# frets-main-board.net
KiCad netlist of a schematic drawn in EAGLE
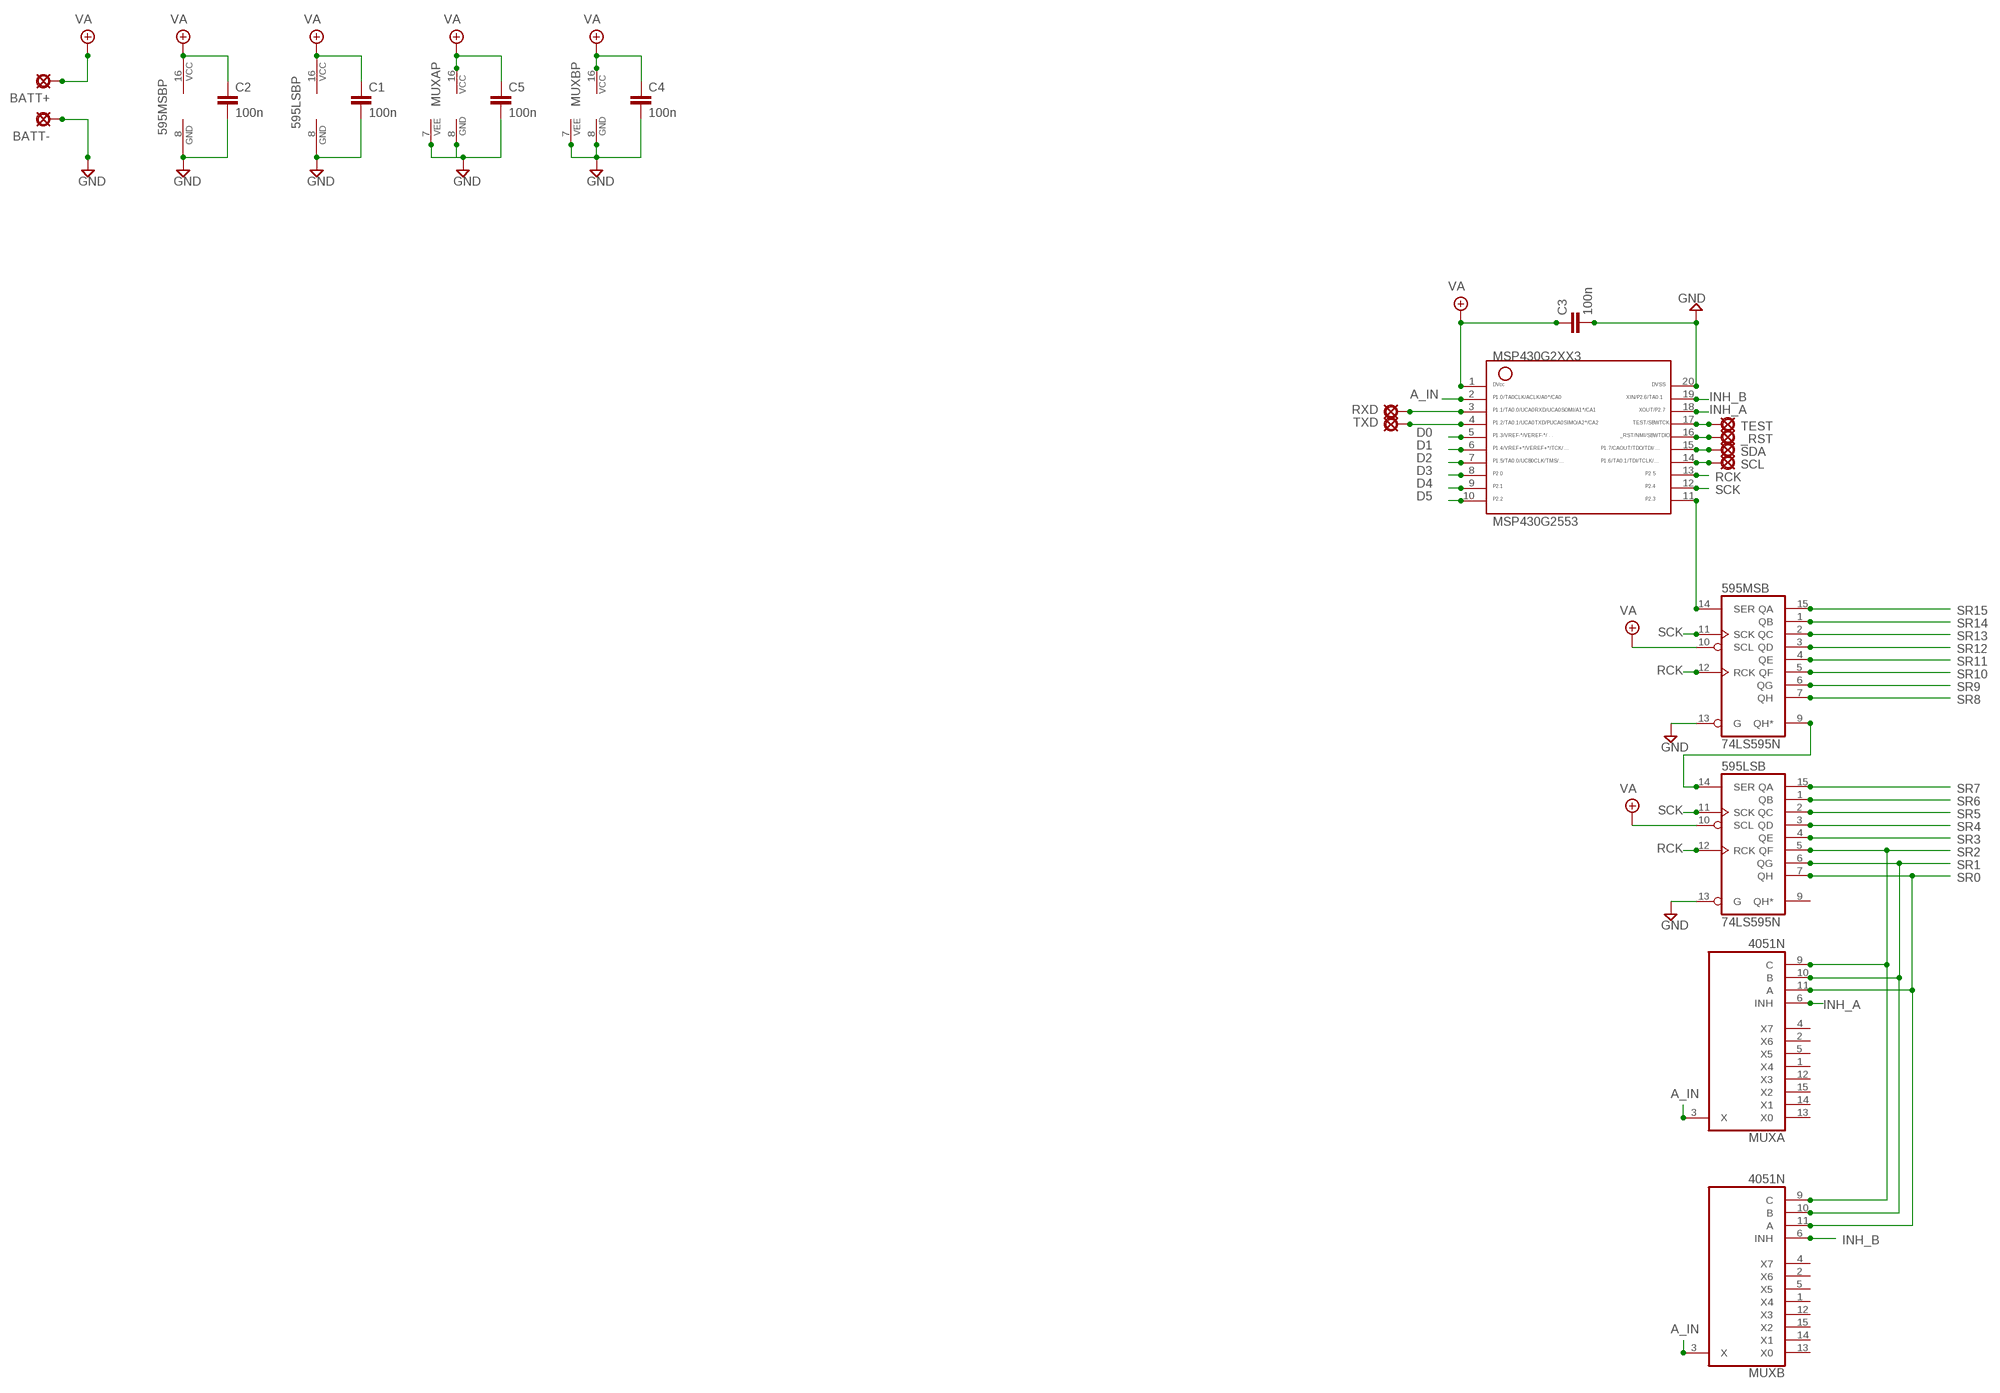
[diagram p0: schematic, sheet 1]

(export (version "E")
  (design (tool "Eeschema 10.0.6"))
  (components
    (comp (ref "595LSB")
      (value "74LS595N")
      (footprint "eagle-import:DIL16")
      (libsource (lib "eagle-import") (part "74595NLS"))
    )
    (comp (ref "595MSB")
      (value "74LS595N")
      (footprint "eagle-import:DIL16")
      (libsource (lib "eagle-import") (part "74595NLS"))
    )
    (comp (ref "BATT+")
      (value "PADL")
      (footprint "eagle-import:LONG")
      (libsource (lib "eagle-import") (part "PADL"))
    )
    (comp (ref "BATT-")
      (value "PADL")
      (footprint "eagle-import:LONG")
      (libsource (lib "eagle-import") (part "PADL"))
    )
    (comp (ref "C1")
      (value "100n")
      (footprint "eagle-import:050X030_050_3")
      (libsource (lib "eagle-import") (part "050X030_050"))
    )
    (comp (ref "C2")
      (value "100n")
      (footprint "eagle-import:050X030_050_3")
      (libsource (lib "eagle-import") (part "050X030_050"))
    )
    (comp (ref "C3")
      (value "100n")
      (footprint "eagle-import:050X030_050_3")
      (libsource (lib "eagle-import") (part "050X030_050"))
    )
    (comp (ref "C4")
      (value "100n")
      (footprint "eagle-import:050X030_050_3")
      (libsource (lib "eagle-import") (part "050X030_050"))
    )
    (comp (ref "C5")
      (value "100n")
      (footprint "eagle-import:050X030_050_3")
      (libsource (lib "eagle-import") (part "050X030_050"))
    )
    (comp (ref "MSP430G2553")
      (value "G2XX3---N20")
      (footprint "eagle-import:N20")
      (libsource (lib "eagle-import") (part "G2XX3---N20"))
    )
    (comp (ref "MUXA")
      (value "4051N")
      (footprint "eagle-import:DIL16")
      (libsource (lib "eagle-import") (part "4051N"))
    )
    (comp (ref "MUXB")
      (value "4051N")
      (footprint "eagle-import:DIL16")
      (libsource (lib "eagle-import") (part "4051N"))
    )
    (comp (ref "RXD")
      (value "PAD")
      (footprint "eagle-import:SQUARE")
      (libsource (lib "eagle-import") (part "PAD"))
    )
    (comp (ref "SCL")
      (value "PAD")
      (footprint "eagle-import:SQUARE")
      (libsource (lib "eagle-import") (part "PAD"))
    )
    (comp (ref "SDA")
      (value "PAD8")
      (footprint "eagle-import:OCTOGON")
      (libsource (lib "eagle-import") (part "PAD8"))
    )
    (comp (ref "TEST")
      (value "PAD8")
      (footprint "eagle-import:OCTOGON")
      (libsource (lib "eagle-import") (part "PAD8"))
    )
    (comp (ref "TXD")
      (value "PAD8")
      (footprint "eagle-import:OCTOGON")
      (libsource (lib "eagle-import") (part "PAD8"))
    )
    (comp (ref "_RST")
      (value "PAD")
      (footprint "eagle-import:SQUARE")
      (libsource (lib "eagle-import") (part "PAD"))
    )
  )
  (nets
    (net (code "1") (name "/A_IN") (class "Default")
      (node (ref "MSP430G2553") (pin "2") (pinfunction "2_2") (pintype "bidirectional"))
      (node (ref "MUXA") (pin "3") (pinfunction "X_3") (pintype "bidirectional"))
      (node (ref "MUXB") (pin "3") (pinfunction "X_3") (pintype "bidirectional"))
    )
    (net (code "2") (name "/D0") (class "Default")
      (node (ref "MSP430G2553") (pin "5") (pinfunction "5_5") (pintype "bidirectional"))
    )
    (net (code "3") (name "/D1") (class "Default")
      (node (ref "MSP430G2553") (pin "6") (pinfunction "6_6") (pintype "bidirectional"))
    )
    (net (code "4") (name "/D2") (class "Default")
      (node (ref "MSP430G2553") (pin "7") (pinfunction "7_7") (pintype "bidirectional"))
    )
    (net (code "5") (name "/D3") (class "Default")
      (node (ref "MSP430G2553") (pin "8") (pinfunction "8_8") (pintype "bidirectional"))
    )
    (net (code "6") (name "/D4") (class "Default")
      (node (ref "MSP430G2553") (pin "9") (pinfunction "9_9") (pintype "bidirectional"))
    )
    (net (code "7") (name "/D5") (class "Default")
      (node (ref "MSP430G2553") (pin "10") (pinfunction "10_10") (pintype "bidirectional"))
    )
    (net (code "8") (name "/INH_A") (class "Default")
      (node (ref "MSP430G2553") (pin "18") (pinfunction "18_18") (pintype "bidirectional"))
      (node (ref "MUXA") (pin "6") (pinfunction "INH_6") (pintype "input"))
    )
    (net (code "9") (name "/INH_B") (class "Default")
      (node (ref "MSP430G2553") (pin "19") (pinfunction "19_19") (pintype "bidirectional"))
      (node (ref "MUXB") (pin "6") (pinfunction "INH_6") (pintype "input"))
    )
    (net (code "10") (name "/RCK") (class "Default")
      (node (ref "595LSB") (pin "12") (pinfunction "RCK_12") (pintype "input"))
      (node (ref "595MSB") (pin "12") (pinfunction "RCK_12") (pintype "input"))
      (node (ref "MSP430G2553") (pin "13") (pinfunction "13_13") (pintype "bidirectional"))
    )
    (net (code "11") (name "/SCK") (class "Default")
      (node (ref "595LSB") (pin "11") (pinfunction "SCK_11") (pintype "input"))
      (node (ref "595MSB") (pin "11") (pinfunction "SCK_11") (pintype "input"))
      (node (ref "MSP430G2553") (pin "12") (pinfunction "12_12") (pintype "bidirectional"))
    )
    (net (code "12") (name "/SR0") (class "Default")
      (node (ref "595LSB") (pin "7") (pinfunction "QH_7") (pintype "tri_state"))
      (node (ref "MUXA") (pin "11") (pinfunction "A_11") (pintype "input"))
      (node (ref "MUXB") (pin "11") (pinfunction "A_11") (pintype "input"))
    )
    (net (code "13") (name "/SR1") (class "Default")
      (node (ref "595LSB") (pin "6") (pinfunction "QG_6") (pintype "tri_state"))
      (node (ref "MUXA") (pin "10") (pinfunction "B_10") (pintype "input"))
      (node (ref "MUXB") (pin "10") (pinfunction "B_10") (pintype "input"))
    )
    (net (code "14") (name "/SR2") (class "Default")
      (node (ref "595LSB") (pin "5") (pinfunction "QF_5") (pintype "tri_state"))
      (node (ref "MUXA") (pin "9") (pinfunction "C_9") (pintype "input"))
      (node (ref "MUXB") (pin "9") (pinfunction "C_9") (pintype "input"))
    )
    (net (code "15") (name "/SR3") (class "Default")
      (node (ref "595LSB") (pin "4") (pinfunction "QE_4") (pintype "tri_state"))
    )
    (net (code "16") (name "/SR4") (class "Default")
      (node (ref "595LSB") (pin "3") (pinfunction "QD_3") (pintype "tri_state"))
    )
    (net (code "17") (name "/SR5") (class "Default")
      (node (ref "595LSB") (pin "2") (pinfunction "QC_2") (pintype "tri_state"))
    )
    (net (code "18") (name "/SR6") (class "Default")
      (node (ref "595LSB") (pin "1") (pinfunction "QB_1") (pintype "tri_state"))
    )
    (net (code "19") (name "/SR7") (class "Default")
      (node (ref "595LSB") (pin "15") (pinfunction "QA_15") (pintype "tri_state"))
    )
    (net (code "20") (name "/SR8") (class "Default")
      (node (ref "595MSB") (pin "7") (pinfunction "QH_7") (pintype "tri_state"))
    )
    (net (code "21") (name "/SR9") (class "Default")
      (node (ref "595MSB") (pin "6") (pinfunction "QG_6") (pintype "tri_state"))
    )
    (net (code "22") (name "/SR10") (class "Default")
      (node (ref "595MSB") (pin "5") (pinfunction "QF_5") (pintype "tri_state"))
    )
    (net (code "23") (name "/SR11") (class "Default")
      (node (ref "595MSB") (pin "4") (pinfunction "QE_4") (pintype "tri_state"))
    )
    (net (code "24") (name "/SR12") (class "Default")
      (node (ref "595MSB") (pin "3") (pinfunction "QD_3") (pintype "tri_state"))
    )
    (net (code "25") (name "/SR13") (class "Default")
      (node (ref "595MSB") (pin "2") (pinfunction "QC_2") (pintype "tri_state"))
    )
    (net (code "26") (name "/SR14") (class "Default")
      (node (ref "595MSB") (pin "1") (pinfunction "QB_1") (pintype "tri_state"))
    )
    (net (code "27") (name "/SR15") (class "Default")
      (node (ref "595MSB") (pin "15") (pinfunction "QA_15") (pintype "tri_state"))
    )
    (net (code "28") (name "GND") (class "Default")
      (node (ref "595LSB") (pin "13") (pinfunction "G_13") (pintype "input"))
      (node (ref "595LSB") (pin "8") (pinfunction "GND_8") (pintype "power_in"))
      (node (ref "595MSB") (pin "13") (pinfunction "G_13") (pintype "input"))
      (node (ref "595MSB") (pin "8") (pinfunction "GND_8") (pintype "power_in"))
      (node (ref "BATT-") (pin "1") (pinfunction "PAD_1") (pintype "passive"))
      (node (ref "C1") (pin "2") (pinfunction "2_2") (pintype "passive"))
      (node (ref "C2") (pin "2") (pinfunction "2_2") (pintype "passive"))
      (node (ref "C3") (pin "2") (pinfunction "2_2") (pintype "passive"))
      (node (ref "C4") (pin "2") (pinfunction "2_2") (pintype "passive"))
      (node (ref "C5") (pin "2") (pinfunction "2_2") (pintype "passive"))
      (node (ref "MSP430G2553") (pin "20") (pinfunction "20_20") (pintype "bidirectional"))
      (node (ref "MUXA") (pin "7") (pinfunction "VEE_7") (pintype "power_in"))
      (node (ref "MUXA") (pin "8") (pinfunction "GND_8") (pintype "power_in"))
      (node (ref "MUXB") (pin "7") (pinfunction "VEE_7") (pintype "power_in"))
      (node (ref "MUXB") (pin "8") (pinfunction "GND_8") (pintype "power_in"))
    )
    (net (code "29") (name "Net-(595LSBA-SER)") (class "Default")
      (node (ref "595LSB") (pin "14") (pinfunction "SER_14") (pintype "input"))
      (node (ref "595MSB") (pin "9") (pinfunction "QH*_9") (pintype "tri_state"))
    )
    (net (code "30") (name "Net-(595MSBA-SER)") (class "Default")
      (node (ref "595MSB") (pin "14") (pinfunction "SER_14") (pintype "input"))
      (node (ref "MSP430G2553") (pin "11") (pinfunction "11_11") (pintype "bidirectional"))
    )
    (net (code "31") (name "Net-(RXD-PAD)") (class "Default")
      (node (ref "MSP430G2553") (pin "3") (pinfunction "3_3") (pintype "bidirectional"))
      (node (ref "RXD") (pin "1") (pinfunction "PAD_1") (pintype "passive"))
    )
    (net (code "32") (name "Net-(SCL-PAD)") (class "Default")
      (node (ref "MSP430G2553") (pin "14") (pinfunction "14_14") (pintype "bidirectional"))
      (node (ref "SCL") (pin "1") (pinfunction "PAD_1") (pintype "passive"))
    )
    (net (code "33") (name "Net-(SDA-PAD)") (class "Default")
      (node (ref "MSP430G2553") (pin "15") (pinfunction "15_15") (pintype "bidirectional"))
      (node (ref "SDA") (pin "1") (pinfunction "PAD_1") (pintype "passive"))
    )
    (net (code "34") (name "Net-(TEST-PAD)") (class "Default")
      (node (ref "MSP430G2553") (pin "17") (pinfunction "17_17") (pintype "bidirectional"))
      (node (ref "TEST") (pin "1") (pinfunction "PAD_1") (pintype "passive"))
    )
    (net (code "35") (name "Net-(TXD-PAD)") (class "Default")
      (node (ref "MSP430G2553") (pin "4") (pinfunction "4_4") (pintype "bidirectional"))
      (node (ref "TXD") (pin "1") (pinfunction "PAD_1") (pintype "passive"))
    )
    (net (code "36") (name "Net-(_RST-PAD)") (class "Default")
      (node (ref "MSP430G2553") (pin "16") (pinfunction "16_16") (pintype "bidirectional"))
      (node (ref "_RST") (pin "1") (pinfunction "PAD_1") (pintype "passive"))
    )
    (net (code "37") (name "VA") (class "Default")
      (node (ref "595LSB") (pin "10") (pinfunction "SCL_10") (pintype "input"))
      (node (ref "595LSB") (pin "16") (pinfunction "VCC_16") (pintype "power_in"))
      (node (ref "595MSB") (pin "10") (pinfunction "SCL_10") (pintype "input"))
      (node (ref "595MSB") (pin "16") (pinfunction "VCC_16") (pintype "power_in"))
      (node (ref "BATT+") (pin "1") (pinfunction "PAD_1") (pintype "passive"))
      (node (ref "C1") (pin "1") (pinfunction "1_1") (pintype "passive"))
      (node (ref "C2") (pin "1") (pinfunction "1_1") (pintype "passive"))
      (node (ref "C3") (pin "1") (pinfunction "1_1") (pintype "passive"))
      (node (ref "C4") (pin "1") (pinfunction "1_1") (pintype "passive"))
      (node (ref "C5") (pin "1") (pinfunction "1_1") (pintype "passive"))
      (node (ref "MSP430G2553") (pin "1") (pinfunction "1_1") (pintype "bidirectional"))
      (node (ref "MUXA") (pin "16") (pinfunction "VCC_16") (pintype "power_in"))
      (node (ref "MUXB") (pin "16") (pinfunction "VCC_16") (pintype "power_in"))
    )
    (net (code "38") (name "unconnected-(595LSBA-QH*-Pad9)") (class "Default")
      (node (ref "595LSB") (pin "9") (pinfunction "QH*_9") (pintype "tri_state"))
    )
    (net (code "39") (name "unconnected-(MUXAA-X0-Pad13)") (class "Default")
      (node (ref "MUXA") (pin "13") (pinfunction "X0_13") (pintype "bidirectional"))
    )
    (net (code "40") (name "unconnected-(MUXAA-X1-Pad14)") (class "Default")
      (node (ref "MUXA") (pin "14") (pinfunction "X1_14") (pintype "bidirectional"))
    )
    (net (code "41") (name "unconnected-(MUXAA-X2-Pad15)") (class "Default")
      (node (ref "MUXA") (pin "15") (pinfunction "X2_15") (pintype "bidirectional"))
    )
    (net (code "42") (name "unconnected-(MUXAA-X3-Pad12)") (class "Default")
      (node (ref "MUXA") (pin "12") (pinfunction "X3_12") (pintype "bidirectional"))
    )
    (net (code "43") (name "unconnected-(MUXAA-X4-Pad1)") (class "Default")
      (node (ref "MUXA") (pin "1") (pinfunction "X4_1") (pintype "bidirectional"))
    )
    (net (code "44") (name "unconnected-(MUXAA-X5-Pad5)") (class "Default")
      (node (ref "MUXA") (pin "5") (pinfunction "X5_5") (pintype "bidirectional"))
    )
    (net (code "45") (name "unconnected-(MUXAA-X6-Pad2)") (class "Default")
      (node (ref "MUXA") (pin "2") (pinfunction "X6_2") (pintype "bidirectional"))
    )
    (net (code "46") (name "unconnected-(MUXAA-X7-Pad4)") (class "Default")
      (node (ref "MUXA") (pin "4") (pinfunction "X7_4") (pintype "bidirectional"))
    )
    (net (code "47") (name "unconnected-(MUXBA-X0-Pad13)") (class "Default")
      (node (ref "MUXB") (pin "13") (pinfunction "X0_13") (pintype "bidirectional"))
    )
    (net (code "48") (name "unconnected-(MUXBA-X1-Pad14)") (class "Default")
      (node (ref "MUXB") (pin "14") (pinfunction "X1_14") (pintype "bidirectional"))
    )
    (net (code "49") (name "unconnected-(MUXBA-X2-Pad15)") (class "Default")
      (node (ref "MUXB") (pin "15") (pinfunction "X2_15") (pintype "bidirectional"))
    )
    (net (code "50") (name "unconnected-(MUXBA-X3-Pad12)") (class "Default")
      (node (ref "MUXB") (pin "12") (pinfunction "X3_12") (pintype "bidirectional"))
    )
    (net (code "51") (name "unconnected-(MUXBA-X4-Pad1)") (class "Default")
      (node (ref "MUXB") (pin "1") (pinfunction "X4_1") (pintype "bidirectional"))
    )
    (net (code "52") (name "unconnected-(MUXBA-X5-Pad5)") (class "Default")
      (node (ref "MUXB") (pin "5") (pinfunction "X5_5") (pintype "bidirectional"))
    )
    (net (code "53") (name "unconnected-(MUXBA-X6-Pad2)") (class "Default")
      (node (ref "MUXB") (pin "2") (pinfunction "X6_2") (pintype "bidirectional"))
    )
    (net (code "54") (name "unconnected-(MUXBA-X7-Pad4)") (class "Default")
      (node (ref "MUXB") (pin "4") (pinfunction "X7_4") (pintype "bidirectional"))
    )
  )
)
